# Button-connections.net
KiCad netlist of a schematic drawn in Altium Designer
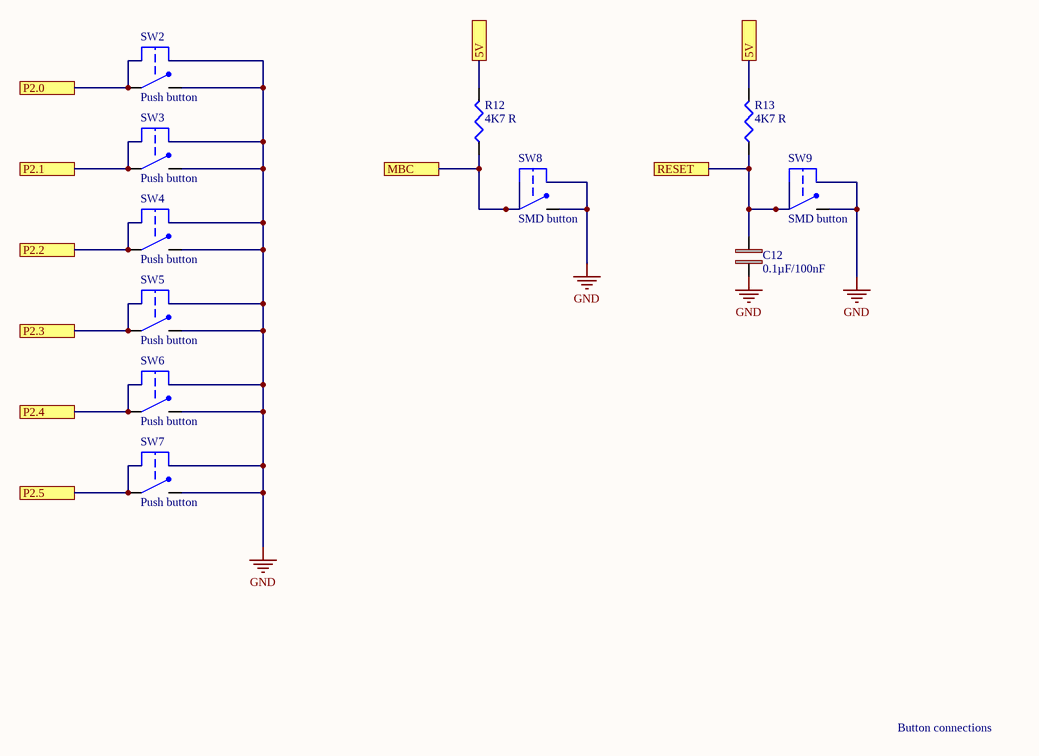
[diagram p0: Button-connections.SchDoc]

(export (version "E")
  (design (tool "Eeschema 10.0.6"))
  (components
    (comp (ref "C12")
      (value "0.1µF/100nF")
      (footprint "MC0603B104K250CT")
      (description "Cap Ceramic 0.1uF 25V X7R 10% Pad SMD 0603 125C T/R")
      (fields
        (field (name "MANUFACTURER") "Multicomp")
        (field (name "MANUFACTURER PART NUMBER") "MC0603B104K250CT")
      )
      (libsource (lib "Tama_Schlib") (part "MC0603B104K250CT"))
    )
    (comp (ref "R12")
      (value "4K7 R")
      (footprint "PCF0603")
      (description "Surface Mount Metal Film Resistor, Pcf Series, 4.7 Kohm, 63 Mw, - 0.1%, 75 V Rohs Compliant: Yes")
      (fields
        (field (name "MANUFACTURER") "TT Welwyn")
        (field (name "MANUFACTURER PART NUMBER") "PCF0603P-R-4K7-BT1")
      )
      (libsource (lib "Tama_Schlib") (part "PCF0603P-R-4K7-BT1"))
    )
    (comp (ref "R13")
      (value "4K7 R")
      (footprint "PCF0603")
      (description "Surface Mount Metal Film Resistor, Pcf Series, 4.7 Kohm, 63 Mw, - 0.1%, 75 V Rohs Compliant: Yes")
      (fields
        (field (name "MANUFACTURER") "TT Welwyn")
        (field (name "MANUFACTURER PART NUMBER") "PCF0603P-R-4K7-BT1")
      )
      (libsource (lib "Tama_Schlib") (part "PCF0603P-R-4K7-BT1"))
    )
    (comp (ref "SW2")
      (value "Push button")
      (footprint "Tactile button")
      (description "Switch Tactile N.O. SPST Round Button PC Pins 0.02A 15VDC 2.6N Thru-Hole Bulk")
      (fields
        (field (name "MANUFACTURER") "Panasonic")
        (field (name "MANUFACTURER PART NUMBER") "EVQ-PAG05R")
      )
      (libsource (lib "Tama_Schlib") (part "EVQ-PAG05R"))
    )
    (comp (ref "SW3")
      (value "Push button")
      (footprint "Tactile button")
      (description "Switch Tactile N.O. SPST Round Button PC Pins 0.02A 15VDC 2.6N Thru-Hole Bulk")
      (fields
        (field (name "MANUFACTURER") "Panasonic")
        (field (name "MANUFACTURER PART NUMBER") "EVQ-PAG05R")
      )
      (libsource (lib "Tama_Schlib") (part "EVQ-PAG05R"))
    )
    (comp (ref "SW4")
      (value "Push button")
      (footprint "Tactile button")
      (description "Switch Tactile N.O. SPST Round Button PC Pins 0.02A 15VDC 2.6N Thru-Hole Bulk")
      (fields
        (field (name "MANUFACTURER") "Panasonic")
        (field (name "MANUFACTURER PART NUMBER") "EVQ-PAG05R")
      )
      (libsource (lib "Tama_Schlib") (part "EVQ-PAG05R"))
    )
    (comp (ref "SW5")
      (value "Push button")
      (footprint "Tactile button")
      (description "Switch Tactile N.O. SPST Round Button PC Pins 0.02A 15VDC 2.6N Thru-Hole Bulk")
      (fields
        (field (name "MANUFACTURER") "Panasonic")
        (field (name "MANUFACTURER PART NUMBER") "EVQ-PAG05R")
      )
      (libsource (lib "Tama_Schlib") (part "EVQ-PAG05R"))
    )
    (comp (ref "SW6")
      (value "Push button")
      (footprint "Tactile button")
      (description "Switch Tactile N.O. SPST Round Button PC Pins 0.02A 15VDC 2.6N Thru-Hole Bulk")
      (fields
        (field (name "MANUFACTURER") "Panasonic")
        (field (name "MANUFACTURER PART NUMBER") "EVQ-PAG05R")
      )
      (libsource (lib "Tama_Schlib") (part "EVQ-PAG05R"))
    )
    (comp (ref "SW7")
      (value "Push button")
      (footprint "Tactile button")
      (description "Switch Tactile N.O. SPST Round Button PC Pins 0.02A 15VDC 2.6N Thru-Hole Bulk")
      (fields
        (field (name "MANUFACTURER") "Panasonic")
        (field (name "MANUFACTURER PART NUMBER") "EVQ-PAG05R")
      )
      (libsource (lib "Tama_Schlib") (part "EVQ-PAG05R"))
    )
    (comp (ref "SW8")
      (value "SMD button")
      (footprint "TACTILE BUTTON - duplicate")
      (description "Switch Tactile N.O. SPST Round Button J-Bend 0.02A 15VDC 2.6N SMD Embossed Tape")
      (fields
        (field (name "MANUFACTURER") "Panasonic")
        (field (name "MANUFACTURER PART NUMBER") "EVQ-PLMA15")
      )
      (libsource (lib "Tama_Schlib") (part "EVQ-PLMA15"))
    )
    (comp (ref "SW9")
      (value "SMD button")
      (footprint "TACTILE BUTTON - duplicate")
      (description "Switch Tactile N.O. SPST Round Button J-Bend 0.02A 15VDC 2.6N SMD Embossed Tape")
      (fields
        (field (name "MANUFACTURER") "Panasonic")
        (field (name "MANUFACTURER PART NUMBER") "EVQ-PLMA15")
      )
      (libsource (lib "Tama_Schlib") (part "EVQ-PLMA15"))
    )
  )
  (nets
    (net (code "1") (name "/5V") (class "Default")
      (node (ref "R12") (pin "2") (pinfunction "2_2") (pintype "passive"))
      (node (ref "R13") (pin "2") (pinfunction "2_2") (pintype "passive"))
    )
    (net (code "2") (name "/MBC") (class "Default")
      (node (ref "R12") (pin "1") (pinfunction "1_1") (pintype "passive"))
      (node (ref "SW8") (pin "1") (pinfunction "1_1") (pintype "passive"))
      (node (ref "SW8") (pin "2") (pinfunction "2_2") (pintype "passive"))
    )
    (net (code "3") (name "/P2.0") (class "Default")
      (node (ref "SW2") (pin "1") (pinfunction "1_1") (pintype "passive"))
      (node (ref "SW2") (pin "2") (pinfunction "2_2") (pintype "passive"))
    )
    (net (code "4") (name "/P2.1") (class "Default")
      (node (ref "SW3") (pin "1") (pinfunction "1_1") (pintype "passive"))
      (node (ref "SW3") (pin "2") (pinfunction "2_2") (pintype "passive"))
    )
    (net (code "5") (name "/P2.2") (class "Default")
      (node (ref "SW4") (pin "1") (pinfunction "1_1") (pintype "passive"))
      (node (ref "SW4") (pin "2") (pinfunction "2_2") (pintype "passive"))
    )
    (net (code "6") (name "/P2.3") (class "Default")
      (node (ref "SW5") (pin "1") (pinfunction "1_1") (pintype "passive"))
      (node (ref "SW5") (pin "2") (pinfunction "2_2") (pintype "passive"))
    )
    (net (code "7") (name "/P2.4") (class "Default")
      (node (ref "SW6") (pin "1") (pinfunction "1_1") (pintype "passive"))
      (node (ref "SW6") (pin "2") (pinfunction "2_2") (pintype "passive"))
    )
    (net (code "8") (name "/P2.5") (class "Default")
      (node (ref "SW7") (pin "1") (pinfunction "1_1") (pintype "passive"))
      (node (ref "SW7") (pin "2") (pinfunction "2_2") (pintype "passive"))
    )
    (net (code "9") (name "/RESET") (class "Default")
      (node (ref "C12") (pin "1") (pinfunction "1_1") (pintype "passive"))
      (node (ref "R13") (pin "1") (pinfunction "1_1") (pintype "passive"))
      (node (ref "SW9") (pin "1") (pinfunction "1_1") (pintype "passive"))
      (node (ref "SW9") (pin "2") (pinfunction "2_2") (pintype "passive"))
    )
    (net (code "10") (name "GND") (class "Default")
      (node (ref "C12") (pin "2") (pinfunction "2_2") (pintype "passive"))
      (node (ref "SW2") (pin "3") (pinfunction "3_3") (pintype "passive"))
      (node (ref "SW2") (pin "4") (pinfunction "4_4") (pintype "passive"))
      (node (ref "SW3") (pin "3") (pinfunction "3_3") (pintype "passive"))
      (node (ref "SW3") (pin "4") (pinfunction "4_4") (pintype "passive"))
      (node (ref "SW4") (pin "3") (pinfunction "3_3") (pintype "passive"))
      (node (ref "SW4") (pin "4") (pinfunction "4_4") (pintype "passive"))
      (node (ref "SW5") (pin "3") (pinfunction "3_3") (pintype "passive"))
      (node (ref "SW5") (pin "4") (pinfunction "4_4") (pintype "passive"))
      (node (ref "SW6") (pin "3") (pinfunction "3_3") (pintype "passive"))
      (node (ref "SW6") (pin "4") (pinfunction "4_4") (pintype "passive"))
      (node (ref "SW7") (pin "3") (pinfunction "3_3") (pintype "passive"))
      (node (ref "SW7") (pin "4") (pinfunction "4_4") (pintype "passive"))
      (node (ref "SW8") (pin "3") (pinfunction "3_3") (pintype "passive"))
      (node (ref "SW8") (pin "4") (pinfunction "4_4") (pintype "passive"))
      (node (ref "SW9") (pin "3") (pinfunction "3_3") (pintype "passive"))
      (node (ref "SW9") (pin "4") (pinfunction "4_4") (pintype "passive"))
    )
  )
)
